# AM27S13.net
KiCad netlist of a schematic drawn in EAGLE
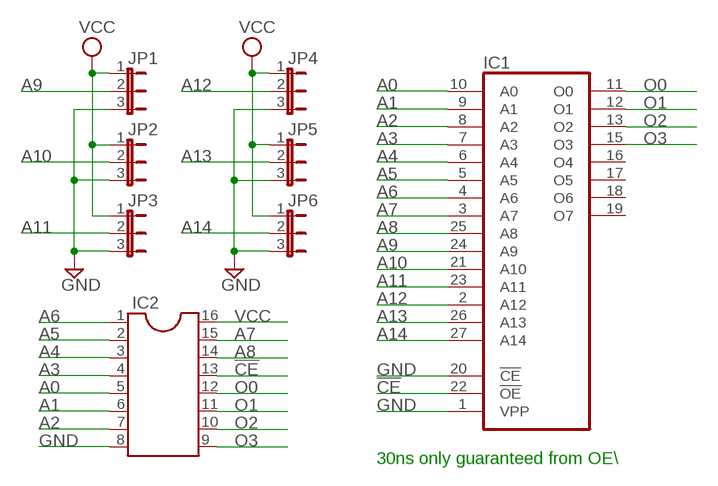
[diagram p0: schematic, sheet 1]

(export (version "E")
  (design (tool "Eeschema 10.0.6"))
  (components
    (comp (ref "IC1")
      (value "27256")
      (footprint "eagle-import:DIL28")
      (libsource (lib "eagle-import") (part "27256"))
    )
    (comp (ref "IC2")
      (value "DIL16")
      (footprint "eagle-import:DIL16")
      (libsource (lib "eagle-import") (part "DIL16"))
    )
    (comp (ref "JP1")
      (value "JP2E")
      (footprint "eagle-import:JP2")
      (libsource (lib "eagle-import") (part "JP2E"))
    )
    (comp (ref "JP2")
      (value "JP2E")
      (footprint "eagle-import:JP2")
      (libsource (lib "eagle-import") (part "JP2E"))
    )
    (comp (ref "JP3")
      (value "JP2E")
      (footprint "eagle-import:JP2")
      (libsource (lib "eagle-import") (part "JP2E"))
    )
    (comp (ref "JP4")
      (value "JP2E")
      (footprint "eagle-import:JP2")
      (libsource (lib "eagle-import") (part "JP2E"))
    )
    (comp (ref "JP5")
      (value "JP2E")
      (footprint "eagle-import:JP2")
      (libsource (lib "eagle-import") (part "JP2E"))
    )
    (comp (ref "JP6")
      (value "JP2E")
      (footprint "eagle-import:JP2")
      (libsource (lib "eagle-import") (part "JP2E"))
    )
  )
  (nets
    (net (code "1") (name "/A0") (class "Default")
      (node (ref "IC1") (pin "10") (pinfunction "A0_10") (pintype "input"))
      (node (ref "IC2") (pin "5") (pinfunction "5_5") (pintype "passive"))
    )
    (net (code "2") (name "/A1") (class "Default")
      (node (ref "IC1") (pin "9") (pinfunction "A1_9") (pintype "input"))
      (node (ref "IC2") (pin "6") (pinfunction "6_6") (pintype "passive"))
    )
    (net (code "3") (name "/A2") (class "Default")
      (node (ref "IC1") (pin "8") (pinfunction "A2_8") (pintype "input"))
      (node (ref "IC2") (pin "7") (pinfunction "7_7") (pintype "passive"))
    )
    (net (code "4") (name "/A3") (class "Default")
      (node (ref "IC1") (pin "7") (pinfunction "A3_7") (pintype "input"))
      (node (ref "IC2") (pin "4") (pinfunction "4_4") (pintype "passive"))
    )
    (net (code "5") (name "/A4") (class "Default")
      (node (ref "IC1") (pin "6") (pinfunction "A4_6") (pintype "input"))
      (node (ref "IC2") (pin "3") (pinfunction "3_3") (pintype "passive"))
    )
    (net (code "6") (name "/A5") (class "Default")
      (node (ref "IC1") (pin "5") (pinfunction "A5_5") (pintype "input"))
      (node (ref "IC2") (pin "2") (pinfunction "2_2") (pintype "passive"))
    )
    (net (code "7") (name "/A6") (class "Default")
      (node (ref "IC1") (pin "4") (pinfunction "A6_4") (pintype "input"))
      (node (ref "IC2") (pin "1") (pinfunction "1_1") (pintype "passive"))
    )
    (net (code "8") (name "/A7") (class "Default")
      (node (ref "IC1") (pin "3") (pinfunction "A7_3") (pintype "input"))
      (node (ref "IC2") (pin "15") (pinfunction "15_15") (pintype "passive"))
    )
    (net (code "9") (name "/A8") (class "Default")
      (node (ref "IC1") (pin "25") (pinfunction "A8_25") (pintype "input"))
      (node (ref "IC2") (pin "14") (pinfunction "14_14") (pintype "passive"))
    )
    (net (code "10") (name "/A9") (class "Default")
      (node (ref "IC1") (pin "24") (pinfunction "A9_24") (pintype "input"))
      (node (ref "JP1") (pin "2") (pinfunction "2_2") (pintype "passive"))
    )
    (net (code "11") (name "/A10") (class "Default")
      (node (ref "IC1") (pin "21") (pinfunction "A10_21") (pintype "input"))
      (node (ref "JP2") (pin "2") (pinfunction "2_2") (pintype "passive"))
    )
    (net (code "12") (name "/A11") (class "Default")
      (node (ref "IC1") (pin "23") (pinfunction "A11_23") (pintype "input"))
      (node (ref "JP3") (pin "2") (pinfunction "2_2") (pintype "passive"))
    )
    (net (code "13") (name "/A12") (class "Default")
      (node (ref "IC1") (pin "2") (pinfunction "A12_2") (pintype "input"))
      (node (ref "JP4") (pin "2") (pinfunction "2_2") (pintype "passive"))
    )
    (net (code "14") (name "/A13") (class "Default")
      (node (ref "IC1") (pin "26") (pinfunction "A13_26") (pintype "input"))
      (node (ref "JP5") (pin "2") (pinfunction "2_2") (pintype "passive"))
    )
    (net (code "15") (name "/A14") (class "Default")
      (node (ref "IC1") (pin "27") (pinfunction "A14_27") (pintype "input"))
      (node (ref "JP6") (pin "2") (pinfunction "2_2") (pintype "passive"))
    )
    (net (code "16") (name "/O0") (class "Default")
      (node (ref "IC1") (pin "11") (pinfunction "O0_11") (pintype "tri_state"))
      (node (ref "IC2") (pin "12") (pinfunction "12_12") (pintype "passive"))
    )
    (net (code "17") (name "/O1") (class "Default")
      (node (ref "IC1") (pin "12") (pinfunction "O1_12") (pintype "tri_state"))
      (node (ref "IC2") (pin "11") (pinfunction "11_11") (pintype "passive"))
    )
    (net (code "18") (name "/O2") (class "Default")
      (node (ref "IC1") (pin "13") (pinfunction "O2_13") (pintype "tri_state"))
      (node (ref "IC2") (pin "10") (pinfunction "10_10") (pintype "passive"))
    )
    (net (code "19") (name "/O3") (class "Default")
      (node (ref "IC1") (pin "15") (pinfunction "O3_15") (pintype "tri_state"))
      (node (ref "IC2") (pin "9") (pinfunction "9_9") (pintype "passive"))
    )
    (net (code "20") (name "/~{CE}") (class "Default")
      (node (ref "IC1") (pin "22") (pinfunction "~{OE}_22") (pintype "input"))
      (node (ref "IC2") (pin "13") (pinfunction "13_13") (pintype "passive"))
    )
    (net (code "21") (name "GND") (class "Default")
      (node (ref "IC1") (pin "1") (pinfunction "VPP_1") (pintype "input"))
      (node (ref "IC1") (pin "20") (pinfunction "~{CE}_20") (pintype "input"))
      (node (ref "IC2") (pin "8") (pinfunction "8_8") (pintype "passive"))
      (node (ref "JP1") (pin "3") (pinfunction "3_3") (pintype "passive"))
      (node (ref "JP2") (pin "3") (pinfunction "3_3") (pintype "passive"))
      (node (ref "JP3") (pin "3") (pinfunction "3_3") (pintype "passive"))
      (node (ref "JP4") (pin "3") (pinfunction "3_3") (pintype "passive"))
      (node (ref "JP5") (pin "3") (pinfunction "3_3") (pintype "passive"))
      (node (ref "JP6") (pin "3") (pinfunction "3_3") (pintype "passive"))
    )
    (net (code "22") (name "VCC") (class "Default")
      (node (ref "IC2") (pin "16") (pinfunction "16_16") (pintype "passive"))
      (node (ref "JP1") (pin "1") (pinfunction "1_1") (pintype "passive"))
      (node (ref "JP2") (pin "1") (pinfunction "1_1") (pintype "passive"))
      (node (ref "JP3") (pin "1") (pinfunction "1_1") (pintype "passive"))
      (node (ref "JP4") (pin "1") (pinfunction "1_1") (pintype "passive"))
      (node (ref "JP5") (pin "1") (pinfunction "1_1") (pintype "passive"))
      (node (ref "JP6") (pin "1") (pinfunction "1_1") (pintype "passive"))
    )
    (net (code "23") (name "unconnected-(IC1A-O4-Pad16)") (class "Default")
      (node (ref "IC1") (pin "16") (pinfunction "O4_16") (pintype "tri_state"))
    )
    (net (code "24") (name "unconnected-(IC1A-O5-Pad17)") (class "Default")
      (node (ref "IC1") (pin "17") (pinfunction "O5_17") (pintype "tri_state"))
    )
    (net (code "25") (name "unconnected-(IC1A-O6-Pad18)") (class "Default")
      (node (ref "IC1") (pin "18") (pinfunction "O6_18") (pintype "tri_state"))
    )
    (net (code "26") (name "unconnected-(IC1A-O7-Pad19)") (class "Default")
      (node (ref "IC1") (pin "19") (pinfunction "O7_19") (pintype "tri_state"))
    )
  )
)
